# EasyEDA_File.net
KiCad netlist of a schematic drawn in EasyEDA
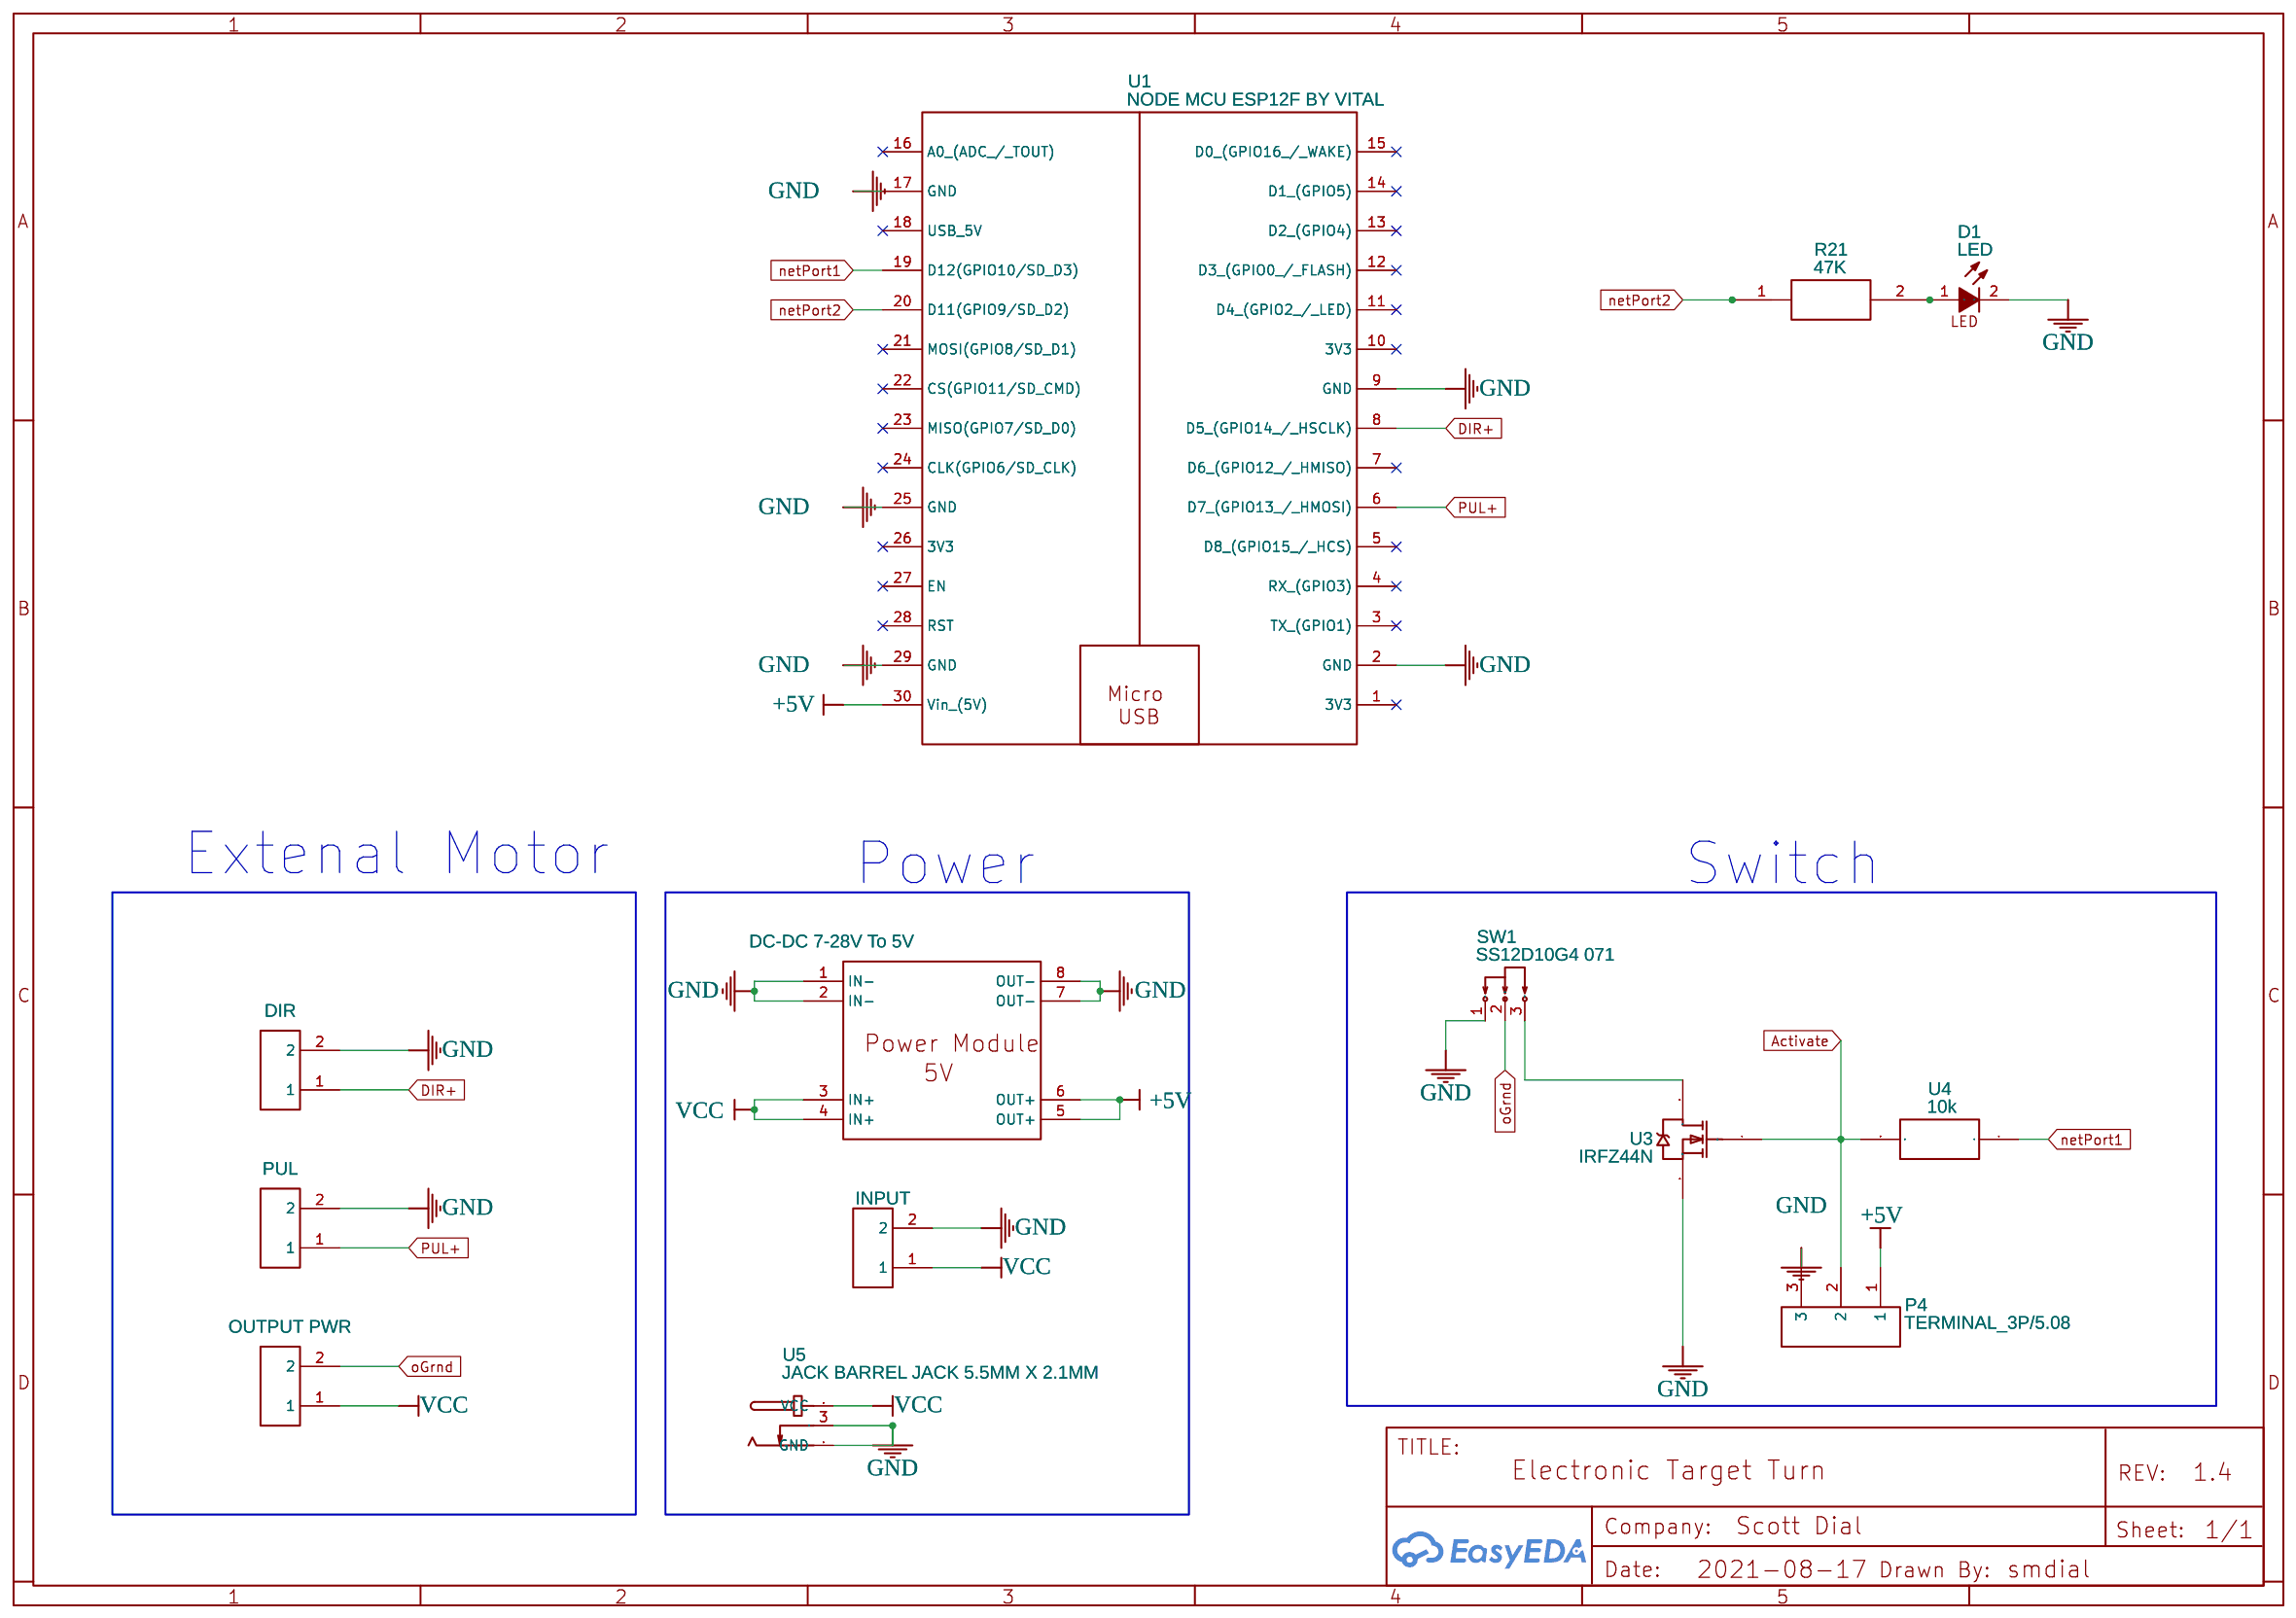
[diagram p0: schematic sheet]

(export (version "E")
  (design (tool "Eeschema 10.0.6"))
  (components
    (comp (ref "D1")
      (value "LED")
      (fields (field (name "BOM_Manufacturer Part") "5600") (field (name "BOM_Supplier Part") "L20325-ND"))
      (libsource (lib "") (part "LED"))
    )
    (comp (ref "P1")
      (value "DIR")
      (fields (field (name "BOM_Manufacturer Part") "Screw terminal 2p"))
      (libsource (lib "") (part "SCREW TERMINAL 2P"))
    )
    (comp (ref "P2")
      (value "PUL")
      (fields (field (name "BOM_Manufacturer Part") "Screw terminal 2p"))
      (libsource (lib "") (part "SCREW TERMINAL 2P"))
    )
    (comp (ref "P3")
      (value "INPUT")
      (fields (field (name "BOM_Manufacturer Part") "Screw terminal 2p"))
      (libsource (lib "") (part "SCREW TERMINAL 2P"))
    )
    (comp (ref "P4")
      (value "TERMINAL_3P/5.08")
      (fields (field (name "BOM_Manufacturer Part") "Screw terminal 3p"))
      (libsource (lib "") (part "TERMINAL_3P/5.08"))
    )
    (comp (ref "P5")
      (value "OUTPUT PWR")
      (fields (field (name "BOM_Manufacturer Part") "Screw terminal 2p"))
      (libsource (lib "") (part "SCREW TERMINAL 2P"))
    )
    (comp (ref "R21") (value "47K") (libsource (lib "") (part "47K")))
    (comp (ref "SW1")
      (value "SS12D10G4 071")
      (fields (field (name "BOM_Supplier Part") "C2887259"))
      (libsource (lib "") (part "SS12D10G4 071"))
    )
    (comp (ref "U1")
      (value "NODE MCU ESP12F BY VITAL")
      (libsource (lib "") (part "NODE MCU ESP12F BY VITAL"))
    )
    (comp (ref "U2")
      (value "DC-DC 7-28V To 5V")
      (fields (field (name "BOM_Manufacturer Part") "DC-DC 7-28V To 5V Step Down Power Supply Module"))
      (libsource (lib "") (part "DC-DC 7-28V To 5V Step Down Power Supply Module"))
    )
    (comp (ref "U3") (value "IRFZ44N") (libsource (lib "") (part "IRFZ44N")))
    (comp (ref "U4") (value "10k") (libsource (lib "") (part "RESISTOR")))
    (comp (ref "U5")
      (value "JACK BARREL JACK 5.5MM X 2.1MM")
      (libsource (lib "") (part "JACK BARREL JACK 5.5MM X 2.1MM"))
    )
  )
  (nets
    (net (code "1") (name "+5V") (class "Default")
      (node (ref "P4") (pin "1") (pinfunction "1_1") (pintype "unspecified"))
      (node (ref "U1") (pin "30") (pinfunction "Vin_(5V)_30") (pintype "unspecified"))
      (node (ref "U2") (pin "5") (pinfunction "OUT+_5") (pintype "unspecified"))
      (node (ref "U2") (pin "6") (pinfunction "OUT+_6") (pintype "unspecified"))
    )
    (net (code "2") (name "Activate") (class "Default")
      (node (ref "P4") (pin "2") (pinfunction "2_2") (pintype "unspecified"))
      (node (ref "U3") (pin "1") (pinfunction "G_1") (pintype "unspecified"))
      (node (ref "U4") (pin "2") (pinfunction "2_2") (pintype "unspecified"))
    )
    (net (code "3") (name "DIR+") (class "Default")
      (node (ref "P1") (pin "1") (pinfunction "1_1") (pintype "unspecified"))
      (node (ref "U1") (pin "8") (pinfunction "D5_(GPIO14_/_HSCLK)_8") (pintype "unspecified"))
    )
    (net (code "4") (name "GND") (class "Default")
      (node (ref "D1") (pin "2") (pinfunction "K_2") (pintype "unspecified"))
      (node (ref "P1") (pin "2") (pinfunction "2_2") (pintype "unspecified"))
      (node (ref "P2") (pin "2") (pinfunction "2_2") (pintype "unspecified"))
      (node (ref "P3") (pin "2") (pinfunction "2_2") (pintype "unspecified"))
      (node (ref "P4") (pin "3") (pinfunction "3_3") (pintype "unspecified"))
      (node (ref "SW1") (pin "1") (pinfunction "1_1") (pintype "unspecified"))
      (node (ref "U1") (pin "17") (pinfunction "GND_17") (pintype "unspecified"))
      (node (ref "U1") (pin "2") (pinfunction "GND_2") (pintype "unspecified"))
      (node (ref "U1") (pin "25") (pinfunction "GND_25") (pintype "unspecified"))
      (node (ref "U1") (pin "29") (pinfunction "GND_29") (pintype "unspecified"))
      (node (ref "U1") (pin "9") (pinfunction "GND_9") (pintype "unspecified"))
      (node (ref "U2") (pin "1") (pinfunction "IN-_1") (pintype "unspecified"))
      (node (ref "U2") (pin "2") (pinfunction "IN-_2") (pintype "unspecified"))
      (node (ref "U2") (pin "7") (pinfunction "OUT-_7") (pintype "unspecified"))
      (node (ref "U2") (pin "8") (pinfunction "OUT-_8") (pintype "unspecified"))
      (node (ref "U3") (pin "3") (pinfunction "S_3") (pintype "unspecified"))
      (node (ref "U5") (pin "2") (pinfunction "GND_2") (pintype "passive"))
      (node (ref "U5") (pin "3") (pinfunction "3_3") (pintype "passive"))
    )
    (net (code "5") (name "Net-(D1-A)") (class "Default")
      (node (ref "D1") (pin "1") (pinfunction "A_1") (pintype "unspecified"))
      (node (ref "R21") (pin "2") (pintype "passive"))
    )
    (net (code "6") (name "Net-(U3-D)") (class "Default")
      (node (ref "SW1") (pin "3") (pinfunction "3_3") (pintype "unspecified"))
      (node (ref "U3") (pin "2") (pinfunction "D_2") (pintype "unspecified"))
    )
    (net (code "7") (name "PUL+") (class "Default")
      (node (ref "P2") (pin "1") (pinfunction "1_1") (pintype "unspecified"))
      (node (ref "U1") (pin "6") (pinfunction "D7_(GPIO13_/_HMOSI)_6") (pintype "unspecified"))
    )
    (net (code "8") (name "VCC") (class "Default")
      (node (ref "P3") (pin "1") (pinfunction "1_1") (pintype "unspecified"))
      (node (ref "P5") (pin "1") (pinfunction "1_1") (pintype "unspecified"))
      (node (ref "U2") (pin "3") (pinfunction "IN+_3") (pintype "unspecified"))
      (node (ref "U2") (pin "4") (pinfunction "IN+_4") (pintype "unspecified"))
      (node (ref "U5") (pin "1") (pinfunction "VCC_1") (pintype "passive"))
    )
    (net (code "9") (name "netPort1") (class "Default")
      (node (ref "U1") (pin "19") (pinfunction "D12(GPIO10/SD_D3)_19") (pintype "unspecified"))
      (node (ref "U4") (pin "1") (pinfunction "1_1") (pintype "unspecified"))
    )
    (net (code "10") (name "netPort2") (class "Default")
      (node (ref "R21") (pin "1") (pintype "passive"))
      (node (ref "U1") (pin "20") (pinfunction "D11(GPIO9/SD_D2)_20") (pintype "unspecified"))
    )
    (net (code "11") (name "oGrnd") (class "Default")
      (node (ref "P5") (pin "2") (pinfunction "2_2") (pintype "unspecified"))
      (node (ref "SW1") (pin "2") (pinfunction "2_2") (pintype "unspecified"))
    )
    (net (code "12") (name "unconnected-(U1-3V3-Pad1)") (class "Default")
      (node (ref "U1") (pin "1") (pinfunction "3V3_1") (pintype "unspecified+no_connect"))
    )
    (net (code "13") (name "unconnected-(U1-3V3-Pad10)") (class "Default")
      (node (ref "U1") (pin "10") (pinfunction "3V3_10") (pintype "unspecified+no_connect"))
    )
    (net (code "14") (name "unconnected-(U1-3V3-Pad26)") (class "Default")
      (node (ref "U1") (pin "26") (pinfunction "3V3_26") (pintype "unspecified+no_connect"))
    )
    (net (code "15") (name "unconnected-(U1-A0_(ADC_{slash}_TOUT)-Pad16)") (class "Default")
      (node (ref "U1") (pin "16") (pinfunction "A0_(ADC_/_TOUT)_16") (pintype "unspecified+no_connect"))
    )
    (net (code "16") (name "unconnected-(U1-CLK(GPIO6{slash}SD_CLK)-Pad24)") (class "Default")
      (node (ref "U1") (pin "24") (pinfunction "CLK(GPIO6/SD_CLK)_24") (pintype "unspecified+no_connect"))
    )
    (net (code "17") (name "unconnected-(U1-CS(GPIO11{slash}SD_CMD)-Pad22)") (class "Default")
      (node (ref "U1") (pin "22") (pinfunction "CS(GPIO11/SD_CMD)_22") (pintype "unspecified+no_connect"))
    )
    (net (code "18") (name "unconnected-(U1-D0_(GPIO16_{slash}_WAKE)-Pad15)") (class "Default")
      (node (ref "U1") (pin "15") (pinfunction "D0_(GPIO16_/_WAKE)_15") (pintype "unspecified+no_connect"))
    )
    (net (code "19") (name "unconnected-(U1-D1_(GPIO5)-Pad14)") (class "Default")
      (node (ref "U1") (pin "14") (pinfunction "D1_(GPIO5)_14") (pintype "unspecified+no_connect"))
    )
    (net (code "20") (name "unconnected-(U1-D2_(GPIO4)-Pad13)") (class "Default")
      (node (ref "U1") (pin "13") (pinfunction "D2_(GPIO4)_13") (pintype "unspecified+no_connect"))
    )
    (net (code "21") (name "unconnected-(U1-D3_(GPIO0_{slash}_FLASH)-Pad12)") (class "Default")
      (node (ref "U1") (pin "12") (pinfunction "D3_(GPIO0_/_FLASH)_12") (pintype "unspecified+no_connect"))
    )
    (net (code "22") (name "unconnected-(U1-D4_(GPIO2_{slash}_LED)-Pad11)") (class "Default")
      (node (ref "U1") (pin "11") (pinfunction "D4_(GPIO2_/_LED)_11") (pintype "unspecified+no_connect"))
    )
    (net (code "23") (name "unconnected-(U1-D6_(GPIO12_{slash}_HMISO)-Pad7)") (class "Default")
      (node (ref "U1") (pin "7") (pinfunction "D6_(GPIO12_/_HMISO)_7") (pintype "unspecified+no_connect"))
    )
    (net (code "24") (name "unconnected-(U1-D8_(GPIO15_{slash}_HCS)-Pad5)") (class "Default")
      (node (ref "U1") (pin "5") (pinfunction "D8_(GPIO15_/_HCS)_5") (pintype "unspecified+no_connect"))
    )
    (net (code "25") (name "unconnected-(U1-EN-Pad27)") (class "Default")
      (node (ref "U1") (pin "27") (pinfunction "EN_27") (pintype "unspecified+no_connect"))
    )
    (net (code "26") (name "unconnected-(U1-MISO(GPIO7{slash}SD_D0)-Pad23)") (class "Default")
      (node (ref "U1") (pin "23") (pinfunction "MISO(GPIO7/SD_D0)_23") (pintype "unspecified+no_connect"))
    )
    (net (code "27") (name "unconnected-(U1-MOSI(GPIO8{slash}SD_D1)-Pad21)") (class "Default")
      (node (ref "U1") (pin "21") (pinfunction "MOSI(GPIO8/SD_D1)_21") (pintype "unspecified+no_connect"))
    )
    (net (code "28") (name "unconnected-(U1-RST-Pad28)") (class "Default")
      (node (ref "U1") (pin "28") (pinfunction "RST_28") (pintype "unspecified+no_connect"))
    )
    (net (code "29") (name "unconnected-(U1-RX_(GPIO3)-Pad4)") (class "Default")
      (node (ref "U1") (pin "4") (pinfunction "RX_(GPIO3)_4") (pintype "unspecified+no_connect"))
    )
    (net (code "30") (name "unconnected-(U1-TX_(GPIO1)-Pad3)") (class "Default")
      (node (ref "U1") (pin "3") (pinfunction "TX_(GPIO1)_3") (pintype "unspecified+no_connect"))
    )
    (net (code "31") (name "unconnected-(U1-USB_5V-Pad18)") (class "Default")
      (node (ref "U1") (pin "18") (pinfunction "USB_5V_18") (pintype "unspecified+no_connect"))
    )
  )
)
